# SterownikOswietlenia.net
KiCad netlist of a schematic drawn in EAGLE
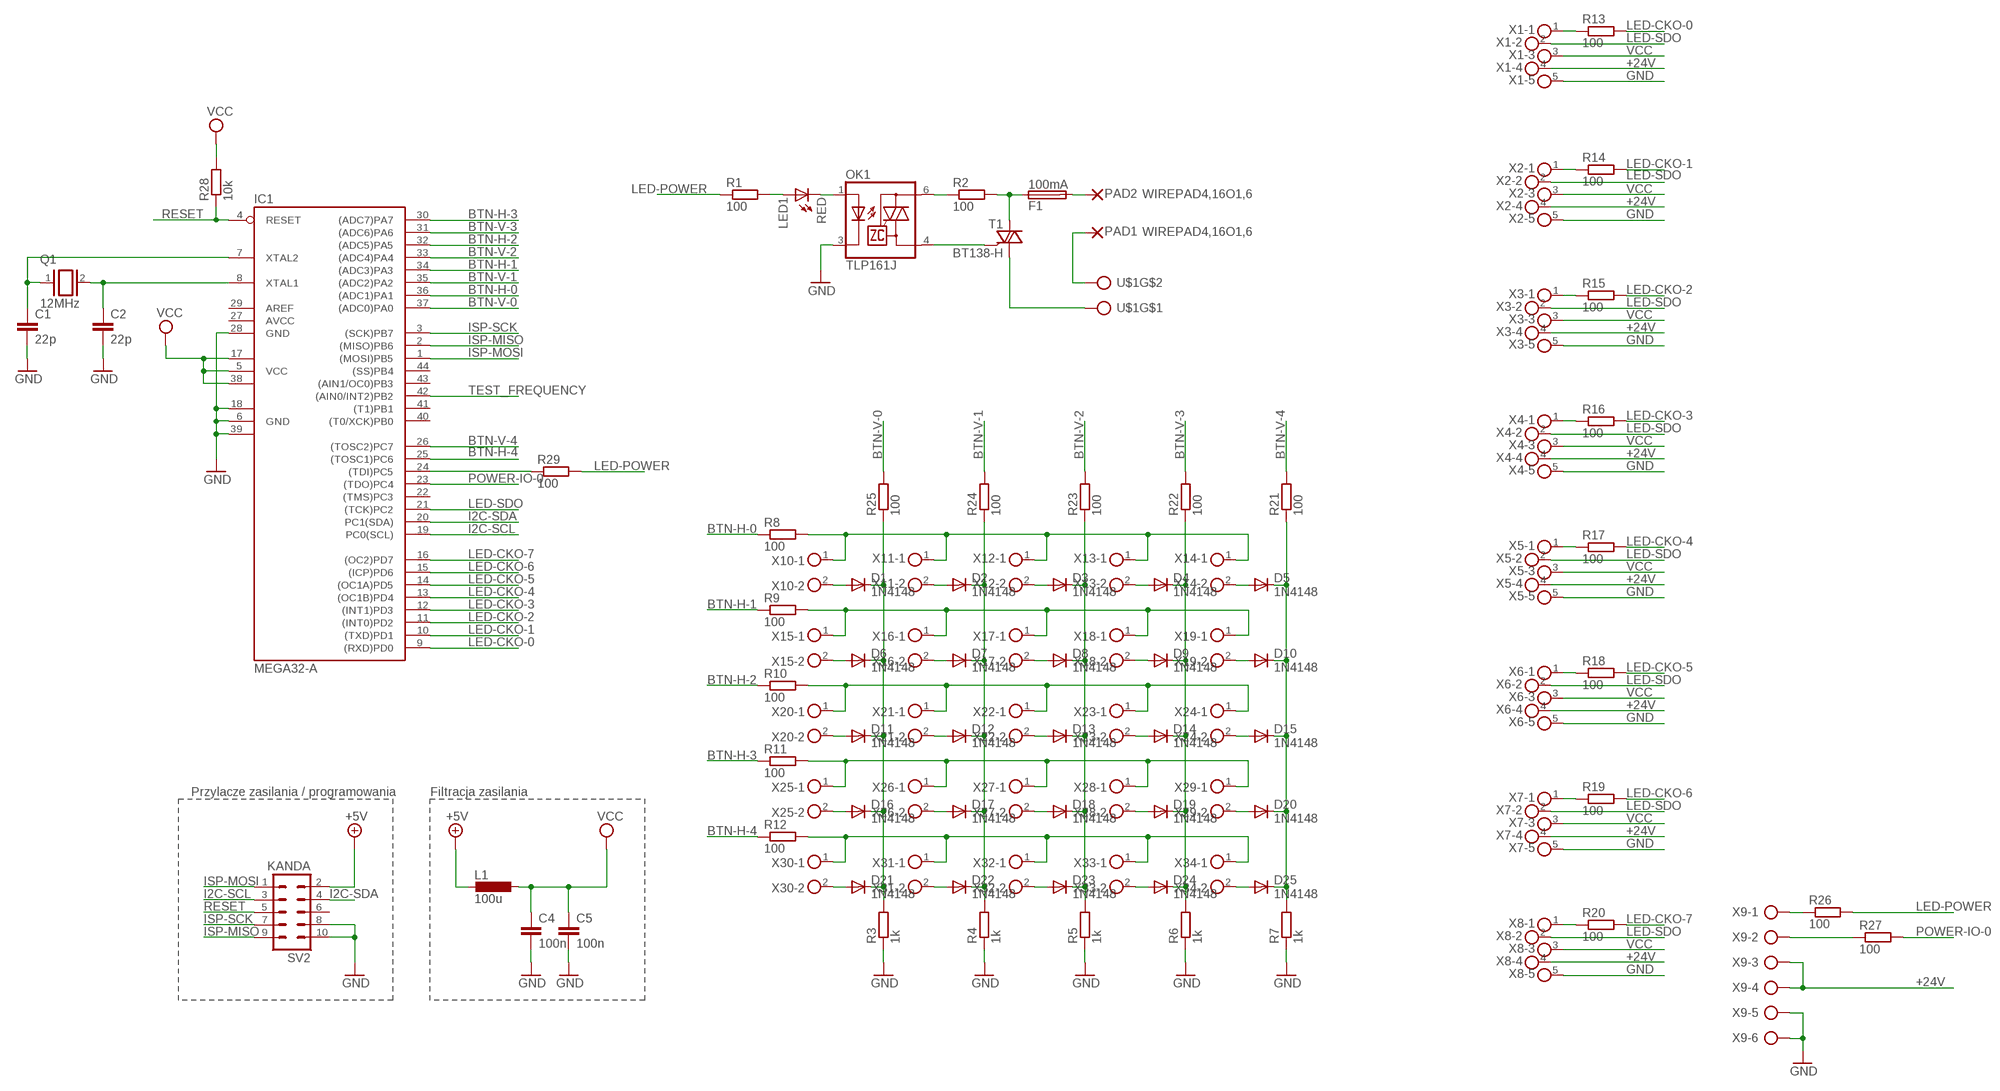
[diagram p0: schematic, sheet 1]

(export (version "E")
  (design (tool "Eeschema 10.0.6"))
  (components
    (comp (ref "C1")
      (value "22p")
      (footprint "eagle-import:C1206")
      (libsource (lib "eagle-import") (part "C-EUC1206"))
    )
    (comp (ref "C2")
      (value "22p")
      (footprint "eagle-import:C1206")
      (libsource (lib "eagle-import") (part "C-EUC1206"))
    )
    (comp (ref "C4")
      (value "100n")
      (footprint "eagle-import:C1206")
      (libsource (lib "eagle-import") (part "C-EUC1206"))
    )
    (comp (ref "C5")
      (value "100n")
      (footprint "eagle-import:C1206")
      (libsource (lib "eagle-import") (part "C-EUC1206"))
    )
    (comp (ref "D1")
      (value "1N4148")
      (footprint "eagle-import:MINIMELF")
      (libsource (lib "eagle-import") (part "DIODE-MINIMELF"))
    )
    (comp (ref "D2")
      (value "1N4148")
      (footprint "eagle-import:MINIMELF")
      (libsource (lib "eagle-import") (part "DIODE-MINIMELF"))
    )
    (comp (ref "D3")
      (value "1N4148")
      (footprint "eagle-import:MINIMELF")
      (libsource (lib "eagle-import") (part "DIODE-MINIMELF"))
    )
    (comp (ref "D4")
      (value "1N4148")
      (footprint "eagle-import:MINIMELF")
      (libsource (lib "eagle-import") (part "DIODE-MINIMELF"))
    )
    (comp (ref "D5")
      (value "1N4148")
      (footprint "eagle-import:MINIMELF")
      (libsource (lib "eagle-import") (part "DIODE-MINIMELF"))
    )
    (comp (ref "D6")
      (value "1N4148")
      (footprint "eagle-import:MINIMELF")
      (libsource (lib "eagle-import") (part "DIODE-MINIMELF"))
    )
    (comp (ref "D7")
      (value "1N4148")
      (footprint "eagle-import:MINIMELF")
      (libsource (lib "eagle-import") (part "DIODE-MINIMELF"))
    )
    (comp (ref "D8")
      (value "1N4148")
      (footprint "eagle-import:MINIMELF")
      (libsource (lib "eagle-import") (part "DIODE-MINIMELF"))
    )
    (comp (ref "D9")
      (value "1N4148")
      (footprint "eagle-import:MINIMELF")
      (libsource (lib "eagle-import") (part "DIODE-MINIMELF"))
    )
    (comp (ref "D10")
      (value "1N4148")
      (footprint "eagle-import:MINIMELF")
      (libsource (lib "eagle-import") (part "DIODE-MINIMELF"))
    )
    (comp (ref "D11")
      (value "1N4148")
      (footprint "eagle-import:MINIMELF")
      (libsource (lib "eagle-import") (part "DIODE-MINIMELF"))
    )
    (comp (ref "D12")
      (value "1N4148")
      (footprint "eagle-import:MINIMELF")
      (libsource (lib "eagle-import") (part "DIODE-MINIMELF"))
    )
    (comp (ref "D13")
      (value "1N4148")
      (footprint "eagle-import:MINIMELF")
      (libsource (lib "eagle-import") (part "DIODE-MINIMELF"))
    )
    (comp (ref "D14")
      (value "1N4148")
      (footprint "eagle-import:MINIMELF")
      (libsource (lib "eagle-import") (part "DIODE-MINIMELF"))
    )
    (comp (ref "D15")
      (value "1N4148")
      (footprint "eagle-import:MINIMELF")
      (libsource (lib "eagle-import") (part "DIODE-MINIMELF"))
    )
    (comp (ref "D16")
      (value "1N4148")
      (footprint "eagle-import:MINIMELF")
      (libsource (lib "eagle-import") (part "DIODE-MINIMELF"))
    )
    (comp (ref "D17")
      (value "1N4148")
      (footprint "eagle-import:MINIMELF")
      (libsource (lib "eagle-import") (part "DIODE-MINIMELF"))
    )
    (comp (ref "D18")
      (value "1N4148")
      (footprint "eagle-import:MINIMELF")
      (libsource (lib "eagle-import") (part "DIODE-MINIMELF"))
    )
    (comp (ref "D19")
      (value "1N4148")
      (footprint "eagle-import:MINIMELF")
      (libsource (lib "eagle-import") (part "DIODE-MINIMELF"))
    )
    (comp (ref "D20")
      (value "1N4148")
      (footprint "eagle-import:MINIMELF")
      (libsource (lib "eagle-import") (part "DIODE-MINIMELF"))
    )
    (comp (ref "D21")
      (value "1N4148")
      (footprint "eagle-import:MINIMELF")
      (libsource (lib "eagle-import") (part "DIODE-MINIMELF"))
    )
    (comp (ref "D22")
      (value "1N4148")
      (footprint "eagle-import:MINIMELF")
      (libsource (lib "eagle-import") (part "DIODE-MINIMELF"))
    )
    (comp (ref "D23")
      (value "1N4148")
      (footprint "eagle-import:MINIMELF")
      (libsource (lib "eagle-import") (part "DIODE-MINIMELF"))
    )
    (comp (ref "D24")
      (value "1N4148")
      (footprint "eagle-import:MINIMELF")
      (libsource (lib "eagle-import") (part "DIODE-MINIMELF"))
    )
    (comp (ref "D25")
      (value "1N4148")
      (footprint "eagle-import:MINIMELF")
      (libsource (lib "eagle-import") (part "DIODE-MINIMELF"))
    )
    (comp (ref "F1")
      (value "100mA")
      (footprint "eagle-import:F457")
      (libsource (lib "eagle-import") (part "F457"))
    )
    (comp (ref "IC1")
      (value "MEGA32-A")
      (footprint "eagle-import:TQFP44")
      (fields (field (name "MPN") "ATMEGA32-16AU"))
      (libsource (lib "eagle-import") (part "MEGA32-A"))
    )
    (comp (ref "L1")
      (value "100u")
      (footprint "eagle-import:R1210")
      (libsource (lib "eagle-import") (part "L-EUL1210"))
    )
    (comp (ref "LED1")
      (value "RED")
      (footprint "eagle-import:LED3MM")
      (libsource (lib "eagle-import") (part "LED3MM"))
    )
    (comp (ref "OK1")
      (value "TLP161J")
      (footprint "eagle-import:MFP4")
      (libsource (lib "eagle-import") (part "TLP161J"))
    )
    (comp (ref "PAD1")
      (value "WIREPAD4,16O1,6")
      (footprint "eagle-import:4,16O1,6")
      (libsource (lib "eagle-import") (part "WIREPAD4,16O1,6"))
    )
    (comp (ref "PAD2")
      (value "WIREPAD4,16O1,6")
      (footprint "eagle-import:4,16O1,6")
      (libsource (lib "eagle-import") (part "WIREPAD4,16O1,6"))
    )
    (comp (ref "Q1")
      (value "12MHz")
      (footprint "eagle-import:QS")
      (libsource (lib "eagle-import") (part "XTAL/S"))
    )
    (comp (ref "R1")
      (value "100")
      (footprint "eagle-import:R1206")
      (libsource (lib "eagle-import") (part "R-EU_R1206"))
    )
    (comp (ref "R2")
      (value "100")
      (footprint "eagle-import:R1206")
      (libsource (lib "eagle-import") (part "R-EU_R1206"))
    )
    (comp (ref "R3")
      (value "1k")
      (footprint "eagle-import:R1206")
      (libsource (lib "eagle-import") (part "R-EU_R1206"))
    )
    (comp (ref "R4")
      (value "1k")
      (footprint "eagle-import:R1206")
      (libsource (lib "eagle-import") (part "R-EU_R1206"))
    )
    (comp (ref "R5")
      (value "1k")
      (footprint "eagle-import:R1206")
      (libsource (lib "eagle-import") (part "R-EU_R1206"))
    )
    (comp (ref "R6")
      (value "1k")
      (footprint "eagle-import:R1206")
      (libsource (lib "eagle-import") (part "R-EU_R1206"))
    )
    (comp (ref "R7")
      (value "1k")
      (footprint "eagle-import:R1206")
      (libsource (lib "eagle-import") (part "R-EU_R1206"))
    )
    (comp (ref "R8")
      (value "100")
      (footprint "eagle-import:R1206")
      (libsource (lib "eagle-import") (part "R-EU_R1206"))
    )
    (comp (ref "R9")
      (value "100")
      (footprint "eagle-import:R1206")
      (libsource (lib "eagle-import") (part "R-EU_R1206"))
    )
    (comp (ref "R10")
      (value "100")
      (footprint "eagle-import:R1206")
      (libsource (lib "eagle-import") (part "R-EU_R1206"))
    )
    (comp (ref "R11")
      (value "100")
      (footprint "eagle-import:R1206")
      (libsource (lib "eagle-import") (part "R-EU_R1206"))
    )
    (comp (ref "R12")
      (value "100")
      (footprint "eagle-import:R1206")
      (libsource (lib "eagle-import") (part "R-EU_R1206"))
    )
    (comp (ref "R13")
      (value "100")
      (footprint "eagle-import:R1206")
      (libsource (lib "eagle-import") (part "R-EU_R1206"))
    )
    (comp (ref "R14")
      (value "100")
      (footprint "eagle-import:R1206")
      (libsource (lib "eagle-import") (part "R-EU_R1206"))
    )
    (comp (ref "R15")
      (value "100")
      (footprint "eagle-import:R1206")
      (libsource (lib "eagle-import") (part "R-EU_R1206"))
    )
    (comp (ref "R16")
      (value "100")
      (footprint "eagle-import:R1206")
      (libsource (lib "eagle-import") (part "R-EU_R1206"))
    )
    (comp (ref "R17")
      (value "100")
      (footprint "eagle-import:R1206")
      (libsource (lib "eagle-import") (part "R-EU_R1206"))
    )
    (comp (ref "R18")
      (value "100")
      (footprint "eagle-import:R1206")
      (libsource (lib "eagle-import") (part "R-EU_R1206"))
    )
    (comp (ref "R19")
      (value "100")
      (footprint "eagle-import:R1206")
      (libsource (lib "eagle-import") (part "R-EU_R1206"))
    )
    (comp (ref "R20")
      (value "100")
      (footprint "eagle-import:R1206")
      (libsource (lib "eagle-import") (part "R-EU_R1206"))
    )
    (comp (ref "R21")
      (value "100")
      (footprint "eagle-import:R1206")
      (libsource (lib "eagle-import") (part "R-EU_R1206"))
    )
    (comp (ref "R22")
      (value "100")
      (footprint "eagle-import:R1206")
      (libsource (lib "eagle-import") (part "R-EU_R1206"))
    )
    (comp (ref "R23")
      (value "100")
      (footprint "eagle-import:R1206")
      (libsource (lib "eagle-import") (part "R-EU_R1206"))
    )
    (comp (ref "R24")
      (value "100")
      (footprint "eagle-import:R1206")
      (libsource (lib "eagle-import") (part "R-EU_R1206"))
    )
    (comp (ref "R25")
      (value "100")
      (footprint "eagle-import:R1206")
      (libsource (lib "eagle-import") (part "R-EU_R1206"))
    )
    (comp (ref "R26")
      (value "100")
      (footprint "eagle-import:R1206")
      (libsource (lib "eagle-import") (part "R-EU_R1206"))
    )
    (comp (ref "R27")
      (value "100")
      (footprint "eagle-import:R1206")
      (libsource (lib "eagle-import") (part "R-EU_R1206"))
    )
    (comp (ref "R28")
      (value "10k")
      (footprint "eagle-import:R1206")
      (libsource (lib "eagle-import") (part "R-EU_R1206"))
    )
    (comp (ref "R29")
      (value "100")
      (footprint "eagle-import:R1206")
      (libsource (lib "eagle-import") (part "R-EU_R1206"))
    )
    (comp (ref "SV2")
      (value "KANDA")
      (footprint "eagle-import:ML10L")
      (libsource (lib "eagle-import") (part "ML10L"))
    )
    (comp (ref "T1")
      (value "BT138-H")
      (footprint "eagle-import:TO220BH")
      (libsource (lib "eagle-import") (part "BT138-H"))
    )
    (comp (ref "U$1")
      (value "AK3001-2")
      (footprint "eagle-import:AK3001-2")
      (libsource (lib "eagle-import") (part "AK3001-2"))
    )
    (comp (ref "X1")
      (value "AKL59-05")
      (footprint "eagle-import:5POL35")
      (libsource (lib "eagle-import") (part "AKL59-05"))
    )
    (comp (ref "X2")
      (value "AKL59-05")
      (footprint "eagle-import:5POL35")
      (libsource (lib "eagle-import") (part "AKL59-05"))
    )
    (comp (ref "X3")
      (value "AKL59-05")
      (footprint "eagle-import:5POL35")
      (libsource (lib "eagle-import") (part "AKL59-05"))
    )
    (comp (ref "X4")
      (value "AKL59-05")
      (footprint "eagle-import:5POL35")
      (libsource (lib "eagle-import") (part "AKL59-05"))
    )
    (comp (ref "X5")
      (value "AKL59-05")
      (footprint "eagle-import:5POL35")
      (libsource (lib "eagle-import") (part "AKL59-05"))
    )
    (comp (ref "X6")
      (value "AKL59-05")
      (footprint "eagle-import:5POL35")
      (libsource (lib "eagle-import") (part "AKL59-05"))
    )
    (comp (ref "X7")
      (value "AKL59-05")
      (footprint "eagle-import:5POL35")
      (libsource (lib "eagle-import") (part "AKL59-05"))
    )
    (comp (ref "X8")
      (value "AKL59-05")
      (footprint "eagle-import:5POL35")
      (libsource (lib "eagle-import") (part "AKL59-05"))
    )
    (comp (ref "X9")
      (value "AK500/6")
      (footprint "eagle-import:AK500_6")
      (libsource (lib "eagle-import") (part "AK500/6"))
    )
    (comp (ref "X10")
      (value "AKL59-02")
      (footprint "eagle-import:2POL35")
      (libsource (lib "eagle-import") (part "AKL59-02"))
    )
    (comp (ref "X11")
      (value "AKL59-02")
      (footprint "eagle-import:2POL35")
      (libsource (lib "eagle-import") (part "AKL59-02"))
    )
    (comp (ref "X12")
      (value "AKL59-02")
      (footprint "eagle-import:2POL35")
      (libsource (lib "eagle-import") (part "AKL59-02"))
    )
    (comp (ref "X13")
      (value "AKL59-02")
      (footprint "eagle-import:2POL35")
      (libsource (lib "eagle-import") (part "AKL59-02"))
    )
    (comp (ref "X14")
      (value "AKL59-02")
      (footprint "eagle-import:2POL35")
      (libsource (lib "eagle-import") (part "AKL59-02"))
    )
    (comp (ref "X15")
      (value "AKL59-02")
      (footprint "eagle-import:2POL35")
      (libsource (lib "eagle-import") (part "AKL59-02"))
    )
    (comp (ref "X16")
      (value "AKL59-02")
      (footprint "eagle-import:2POL35")
      (libsource (lib "eagle-import") (part "AKL59-02"))
    )
    (comp (ref "X17")
      (value "AKL59-02")
      (footprint "eagle-import:2POL35")
      (libsource (lib "eagle-import") (part "AKL59-02"))
    )
    (comp (ref "X18")
      (value "AKL59-02")
      (footprint "eagle-import:2POL35")
      (libsource (lib "eagle-import") (part "AKL59-02"))
    )
    (comp (ref "X19")
      (value "AKL59-02")
      (footprint "eagle-import:2POL35")
      (libsource (lib "eagle-import") (part "AKL59-02"))
    )
    (comp (ref "X20")
      (value "AKL59-02")
      (footprint "eagle-import:2POL35")
      (libsource (lib "eagle-import") (part "AKL59-02"))
    )
    (comp (ref "X21")
      (value "AKL59-02")
      (footprint "eagle-import:2POL35")
      (libsource (lib "eagle-import") (part "AKL59-02"))
    )
    (comp (ref "X22")
      (value "AKL59-02")
      (footprint "eagle-import:2POL35")
      (libsource (lib "eagle-import") (part "AKL59-02"))
    )
    (comp (ref "X23")
      (value "AKL59-02")
      (footprint "eagle-import:2POL35")
      (libsource (lib "eagle-import") (part "AKL59-02"))
    )
    (comp (ref "X24")
      (value "AKL59-02")
      (footprint "eagle-import:2POL35")
      (libsource (lib "eagle-import") (part "AKL59-02"))
    )
    (comp (ref "X25")
      (value "AKL59-02")
      (footprint "eagle-import:2POL35")
      (libsource (lib "eagle-import") (part "AKL59-02"))
    )
    (comp (ref "X26")
      (value "AKL59-02")
      (footprint "eagle-import:2POL35")
      (libsource (lib "eagle-import") (part "AKL59-02"))
    )
    (comp (ref "X27")
      (value "AKL59-02")
      (footprint "eagle-import:2POL35")
      (libsource (lib "eagle-import") (part "AKL59-02"))
    )
    (comp (ref "X28")
      (value "AKL59-02")
      (footprint "eagle-import:2POL35")
      (libsource (lib "eagle-import") (part "AKL59-02"))
    )
    (comp (ref "X29")
      (value "AKL59-02")
      (footprint "eagle-import:2POL35")
      (libsource (lib "eagle-import") (part "AKL59-02"))
    )
    (comp (ref "X30")
      (value "AKL59-02")
      (footprint "eagle-import:2POL35")
      (libsource (lib "eagle-import") (part "AKL59-02"))
    )
    (comp (ref "X31")
      (value "AKL59-02")
      (footprint "eagle-import:2POL35")
      (libsource (lib "eagle-import") (part "AKL59-02"))
    )
    (comp (ref "X32")
      (value "AKL59-02")
      (footprint "eagle-import:2POL35")
      (libsource (lib "eagle-import") (part "AKL59-02"))
    )
    (comp (ref "X33")
      (value "AKL59-02")
      (footprint "eagle-import:2POL35")
      (libsource (lib "eagle-import") (part "AKL59-02"))
    )
    (comp (ref "X34")
      (value "AKL59-02")
      (footprint "eagle-import:2POL35")
      (libsource (lib "eagle-import") (part "AKL59-02"))
    )
  )
  (nets
    (net (code "1") (name "+5V") (class "Default")
      (node (ref "L1") (pin "2") (pinfunction "2_2") (pintype "passive"))
      (node (ref "SV2") (pin "2") (pinfunction "2_2") (pintype "passive"))
    )
    (net (code "2") (name "/+24V") (class "Default")
      (node (ref "X1") (pin "4") (pinfunction "1_4") (pintype "passive"))
      (node (ref "X2") (pin "4") (pinfunction "1_4") (pintype "passive"))
      (node (ref "X3") (pin "4") (pinfunction "1_4") (pintype "passive"))
      (node (ref "X4") (pin "4") (pinfunction "1_4") (pintype "passive"))
      (node (ref "X5") (pin "4") (pinfunction "1_4") (pintype "passive"))
      (node (ref "X6") (pin "4") (pinfunction "1_4") (pintype "passive"))
      (node (ref "X7") (pin "4") (pinfunction "1_4") (pintype "passive"))
      (node (ref "X8") (pin "4") (pinfunction "1_4") (pintype "passive"))
      (node (ref "X9") (pin "3") (pinfunction "KL_3") (pintype "passive"))
      (node (ref "X9") (pin "4") (pinfunction "KL_4") (pintype "passive"))
    )
    (net (code "3") (name "/AVCC") (class "Default")
      (node (ref "IC1") (pin "27") (pinfunction "AVCC_27") (pintype "power_in"))
    )
    (net (code "4") (name "/BTN-H-0") (class "Default")
      (node (ref "IC1") (pin "36") (pinfunction "(ADC1)PA1_36") (pintype "bidirectional"))
      (node (ref "R8") (pin "1") (pinfunction "1_1") (pintype "passive"))
    )
    (net (code "5") (name "/BTN-H-1") (class "Default")
      (node (ref "IC1") (pin "34") (pinfunction "(ADC3)PA3_34") (pintype "bidirectional"))
      (node (ref "R9") (pin "1") (pinfunction "1_1") (pintype "passive"))
    )
    (net (code "6") (name "/BTN-H-2") (class "Default")
      (node (ref "IC1") (pin "32") (pinfunction "(ADC5)PA5_32") (pintype "bidirectional"))
      (node (ref "R10") (pin "1") (pinfunction "1_1") (pintype "passive"))
    )
    (net (code "7") (name "/BTN-H-3") (class "Default")
      (node (ref "IC1") (pin "30") (pinfunction "(ADC7)PA7_30") (pintype "bidirectional"))
      (node (ref "R11") (pin "1") (pinfunction "1_1") (pintype "passive"))
    )
    (net (code "8") (name "/BTN-H-4") (class "Default")
      (node (ref "IC1") (pin "25") (pinfunction "(TOSC1)PC6_25") (pintype "bidirectional"))
      (node (ref "R12") (pin "1") (pinfunction "1_1") (pintype "passive"))
    )
    (net (code "9") (name "/BTN-V-0") (class "Default")
      (node (ref "IC1") (pin "37") (pinfunction "(ADC0)PA0_37") (pintype "bidirectional"))
      (node (ref "R25") (pin "2") (pinfunction "2_2") (pintype "passive"))
    )
    (net (code "10") (name "/BTN-V-1") (class "Default")
      (node (ref "IC1") (pin "35") (pinfunction "(ADC2)PA2_35") (pintype "bidirectional"))
      (node (ref "R24") (pin "2") (pinfunction "2_2") (pintype "passive"))
    )
    (net (code "11") (name "/BTN-V-2") (class "Default")
      (node (ref "IC1") (pin "33") (pinfunction "(ADC4)PA4_33") (pintype "bidirectional"))
      (node (ref "R23") (pin "2") (pinfunction "2_2") (pintype "passive"))
    )
    (net (code "12") (name "/BTN-V-3") (class "Default")
      (node (ref "IC1") (pin "31") (pinfunction "(ADC6)PA6_31") (pintype "bidirectional"))
      (node (ref "R22") (pin "2") (pinfunction "2_2") (pintype "passive"))
    )
    (net (code "13") (name "/BTN-V-4") (class "Default")
      (node (ref "IC1") (pin "26") (pinfunction "(TOSC2)PC7_26") (pintype "bidirectional"))
      (node (ref "R21") (pin "2") (pinfunction "2_2") (pintype "passive"))
    )
    (net (code "14") (name "/I2C-SCL") (class "Default")
      (node (ref "IC1") (pin "19") (pinfunction "PC0(SCL)_19") (pintype "bidirectional"))
      (node (ref "SV2") (pin "3") (pinfunction "3_3") (pintype "passive"))
    )
    (net (code "15") (name "/I2C-SDA") (class "Default")
      (node (ref "IC1") (pin "20") (pinfunction "PC1(SDA)_20") (pintype "bidirectional"))
      (node (ref "SV2") (pin "4") (pinfunction "4_4") (pintype "passive"))
    )
    (net (code "16") (name "/ISP-MISO") (class "Default")
      (node (ref "IC1") (pin "2") (pinfunction "(MISO)PB6_2") (pintype "bidirectional"))
      (node (ref "SV2") (pin "9") (pinfunction "9_9") (pintype "passive"))
    )
    (net (code "17") (name "/ISP-MOSI") (class "Default")
      (node (ref "IC1") (pin "1") (pinfunction "(MOSI)PB5_1") (pintype "bidirectional"))
      (node (ref "SV2") (pin "1") (pinfunction "1_1") (pintype "passive"))
    )
    (net (code "18") (name "/ISP-SCK") (class "Default")
      (node (ref "IC1") (pin "3") (pinfunction "(SCK)PB7_3") (pintype "bidirectional"))
      (node (ref "SV2") (pin "7") (pinfunction "7_7") (pintype "passive"))
    )
    (net (code "19") (name "/LED-CKO-0") (class "Default")
      (node (ref "IC1") (pin "9") (pinfunction "(RXD)PD0_9") (pintype "bidirectional"))
      (node (ref "R13") (pin "2") (pinfunction "2_2") (pintype "passive"))
    )
    (net (code "20") (name "/LED-CKO-1") (class "Default")
      (node (ref "IC1") (pin "10") (pinfunction "(TXD)PD1_10") (pintype "bidirectional"))
      (node (ref "R14") (pin "2") (pinfunction "2_2") (pintype "passive"))
    )
    (net (code "21") (name "/LED-CKO-2") (class "Default")
      (node (ref "IC1") (pin "11") (pinfunction "(INT0)PD2_11") (pintype "bidirectional"))
      (node (ref "R15") (pin "2") (pinfunction "2_2") (pintype "passive"))
    )
    (net (code "22") (name "/LED-CKO-3") (class "Default")
      (node (ref "IC1") (pin "12") (pinfunction "(INT1)PD3_12") (pintype "bidirectional"))
      (node (ref "R16") (pin "2") (pinfunction "2_2") (pintype "passive"))
    )
    (net (code "23") (name "/LED-CKO-4") (class "Default")
      (node (ref "IC1") (pin "13") (pinfunction "(OC1B)PD4_13") (pintype "bidirectional"))
      (node (ref "R17") (pin "2") (pinfunction "2_2") (pintype "passive"))
    )
    (net (code "24") (name "/LED-CKO-5") (class "Default")
      (node (ref "IC1") (pin "14") (pinfunction "(OC1A)PD5_14") (pintype "bidirectional"))
      (node (ref "R18") (pin "2") (pinfunction "2_2") (pintype "passive"))
    )
    (net (code "25") (name "/LED-CKO-6") (class "Default")
      (node (ref "IC1") (pin "15") (pinfunction "(ICP)PD6_15") (pintype "bidirectional"))
      (node (ref "R19") (pin "2") (pinfunction "2_2") (pintype "passive"))
    )
    (net (code "26") (name "/LED-CKO-7") (class "Default")
      (node (ref "IC1") (pin "16") (pinfunction "(OC2)PD7_16") (pintype "bidirectional"))
      (node (ref "R20") (pin "2") (pinfunction "2_2") (pintype "passive"))
    )
    (net (code "27") (name "/LED-POWER") (class "Default")
      (node (ref "R1") (pin "1") (pinfunction "1_1") (pintype "passive"))
      (node (ref "R26") (pin "2") (pinfunction "2_2") (pintype "passive"))
      (node (ref "R29") (pin "2") (pinfunction "2_2") (pintype "passive"))
    )
    (net (code "28") (name "/LED-SDO") (class "Default")
      (node (ref "IC1") (pin "21") (pinfunction "(TCK)PC2_21") (pintype "bidirectional"))
      (node (ref "X1") (pin "2") (pinfunction "1_2") (pintype "passive"))
      (node (ref "X2") (pin "2") (pinfunction "1_2") (pintype "passive"))
      (node (ref "X3") (pin "2") (pinfunction "1_2") (pintype "passive"))
      (node (ref "X4") (pin "2") (pinfunction "1_2") (pintype "passive"))
      (node (ref "X5") (pin "2") (pinfunction "1_2") (pintype "passive"))
      (node (ref "X6") (pin "2") (pinfunction "1_2") (pintype "passive"))
      (node (ref "X7") (pin "2") (pinfunction "1_2") (pintype "passive"))
      (node (ref "X8") (pin "2") (pinfunction "1_2") (pintype "passive"))
    )
    (net (code "29") (name "/POWER-IO-0") (class "Default")
      (node (ref "IC1") (pin "23") (pinfunction "(TDO)PC4_23") (pintype "bidirectional"))
      (node (ref "R27") (pin "2") (pinfunction "2_2") (pintype "passive"))
    )
    (net (code "30") (name "/RESET") (class "Default")
      (node (ref "IC1") (pin "4") (pinfunction "RESET_4") (pintype "input"))
      (node (ref "R28") (pin "1") (pinfunction "1_1") (pintype "passive"))
      (node (ref "SV2") (pin "5") (pinfunction "5_5") (pintype "passive"))
    )
    (net (code "31") (name "/TEST_FREQUENCY") (class "Default")
      (node (ref "IC1") (pin "42") (pinfunction "(AIN0/INT2)PB2_42") (pintype "bidirectional"))
    )
    (net (code "32") (name "GND") (class "Default")
      (node (ref "C1") (pin "2") (pinfunction "2_2") (pintype "passive"))
      (node (ref "C2") (pin "2") (pinfunction "2_2") (pintype "passive"))
      (node (ref "C4") (pin "2") (pinfunction "2_2") (pintype "passive"))
      (node (ref "C5") (pin "2") (pinfunction "2_2") (pintype "passive"))
      (node (ref "IC1") (pin "18") (pinfunction "GND1_18") (pintype "power_in"))
      (node (ref "IC1") (pin "28") (pinfunction "GND_28") (pintype "power_in"))
      (node (ref "IC1") (pin "39") (pinfunction "GND2_39") (pintype "power_in"))
      (node (ref "IC1") (pin "6") (pinfunction "GND_6") (pintype "power_in"))
      (node (ref "OK1") (pin "3") (pinfunction "C_3") (pintype "passive"))
      (node (ref "R3") (pin "1") (pinfunction "1_1") (pintype "passive"))
      (node (ref "R4") (pin "1") (pinfunction "1_1") (pintype "passive"))
      (node (ref "R5") (pin "1") (pinfunction "1_1") (pintype "passive"))
      (node (ref "R6") (pin "1") (pinfunction "1_1") (pintype "passive"))
      (node (ref "R7") (pin "1") (pinfunction "1_1") (pintype "passive"))
      (node (ref "SV2") (pin "10") (pinfunction "10_10") (pintype "passive"))
      (node (ref "SV2") (pin "8") (pinfunction "8_8") (pintype "passive"))
      (node (ref "X1") (pin "5") (pinfunction "1_5") (pintype "passive"))
      (node (ref "X2") (pin "5") (pinfunction "1_5") (pintype "passive"))
      (node (ref "X3") (pin "5") (pinfunction "1_5") (pintype "passive"))
      (node (ref "X4") (pin "5") (pinfunction "1_5") (pintype "passive"))
      (node (ref "X5") (pin "5") (pinfunction "1_5") (pintype "passive"))
      (node (ref "X6") (pin "5") (pinfunction "1_5") (pintype "passive"))
      (node (ref "X7") (pin "5") (pinfunction "1_5") (pintype "passive"))
      (node (ref "X8") (pin "5") (pinfunction "1_5") (pintype "passive"))
      (node (ref "X9") (pin "5") (pinfunction "KL_5") (pintype "passive"))
      (node (ref "X9") (pin "6") (pinfunction "KL_6") (pintype "passive"))
    )
    (net (code "33") (name "Net-(D1-PadC)") (class "Default")
      (node (ref "D1") (pin "C") (pinfunction "C_C") (pintype "passive"))
      (node (ref "D11") (pin "C") (pinfunction "C_C") (pintype "passive"))
      (node (ref "D16") (pin "C") (pinfunction "C_C") (pintype "passive"))
      (node (ref "D21") (pin "C") (pinfunction "C_C") (pintype "passive"))
      (node (ref "D6") (pin "C") (pinfunction "C_C") (pintype "passive"))
      (node (ref "R25") (pin "1") (pinfunction "1_1") (pintype "passive"))
      (node (ref "R3") (pin "2") (pinfunction "2_2") (pintype "passive"))
    )
    (net (code "34") (name "Net-(D10-PadC)") (class "Default")
      (node (ref "D10") (pin "C") (pinfunction "C_C") (pintype "passive"))
      (node (ref "D15") (pin "C") (pinfunction "C_C") (pintype "passive"))
      (node (ref "D20") (pin "C") (pinfunction "C_C") (pintype "passive"))
      (node (ref "D25") (pin "C") (pinfunction "C_C") (pintype "passive"))
      (node (ref "D5") (pin "C") (pinfunction "C_C") (pintype "passive"))
      (node (ref "R21") (pin "1") (pinfunction "1_1") (pintype "passive"))
      (node (ref "R7") (pin "2") (pinfunction "2_2") (pintype "passive"))
    )
    (net (code "35") (name "Net-(D12-PadC)") (class "Default")
      (node (ref "D12") (pin "C") (pinfunction "C_C") (pintype "passive"))
      (node (ref "D17") (pin "C") (pinfunction "C_C") (pintype "passive"))
      (node (ref "D2") (pin "C") (pinfunction "C_C") (pintype "passive"))
      (node (ref "D22") (pin "C") (pinfunction "C_C") (pintype "passive"))
      (node (ref "D7") (pin "C") (pinfunction "C_C") (pintype "passive"))
      (node (ref "R24") (pin "1") (pinfunction "1_1") (pintype "passive"))
      (node (ref "R4") (pin "2") (pinfunction "2_2") (pintype "passive"))
    )
    (net (code "36") (name "Net-(D13-PadC)") (class "Default")
      (node (ref "D13") (pin "C") (pinfunction "C_C") (pintype "passive"))
      (node (ref "D18") (pin "C") (pinfunction "C_C") (pintype "passive"))
      (node (ref "D23") (pin "C") (pinfunction "C_C") (pintype "passive"))
      (node (ref "D3") (pin "C") (pinfunction "C_C") (pintype "passive"))
      (node (ref "D8") (pin "C") (pinfunction "C_C") (pintype "passive"))
      (node (ref "R23") (pin "1") (pinfunction "1_1") (pintype "passive"))
      (node (ref "R5") (pin "2") (pinfunction "2_2") (pintype "passive"))
    )
    (net (code "37") (name "Net-(D14-PadC)") (class "Default")
      (node (ref "D14") (pin "C") (pinfunction "C_C") (pintype "passive"))
      (node (ref "D19") (pin "C") (pinfunction "C_C") (pintype "passive"))
      (node (ref "D24") (pin "C") (pinfunction "C_C") (pintype "passive"))
      (node (ref "D4") (pin "C") (pinfunction "C_C") (pintype "passive"))
      (node (ref "D9") (pin "C") (pinfunction "C_C") (pintype "passive"))
      (node (ref "R22") (pin "1") (pinfunction "1_1") (pintype "passive"))
      (node (ref "R6") (pin "2") (pinfunction "2_2") (pintype "passive"))
    )
    (net (code "38") (name "Net-(IC1-(TDI)PC5)") (class "Default")
      (node (ref "IC1") (pin "24") (pinfunction "(TDI)PC5_24") (pintype "bidirectional"))
      (node (ref "R29") (pin "1") (pinfunction "1_1") (pintype "passive"))
    )
    (net (code "39") (name "Net-(IC1-XTAL1)") (class "Default")
      (node (ref "C2") (pin "1") (pinfunction "1_1") (pintype "passive"))
      (node (ref "IC1") (pin "8") (pinfunction "XTAL1_8") (pintype "bidirectional"))
      (node (ref "Q1") (pin "2") (pinfunction "2_2") (pintype "passive"))
    )
    (net (code "40") (name "Net-(IC1-XTAL2)") (class "Default")
      (node (ref "C1") (pin "1") (pinfunction "1_1") (pintype "passive"))
      (node (ref "IC1") (pin "7") (pinfunction "XTAL2_7") (pintype "bidirectional"))
      (node (ref "Q1") (pin "1") (pinfunction "1_1") (pintype "passive"))
    )
    (net (code "41") (name "Net-(LED1-C)") (class "Default")
      (node (ref "LED1") (pin "K") (pinfunction "C_K") (pintype "passive"))
      (node (ref "OK1") (pin "1") (pinfunction "A_1") (pintype "passive"))
    )
    (net (code "42") (name "Net-(LED1-PadA)") (class "Default")
      (node (ref "LED1") (pin "A") (pinfunction "A_A") (pintype "passive"))
      (node (ref "R1") (pin "2") (pinfunction "2_2") (pintype "passive"))
    )
    (net (code "43") (name "Net-(OK1-A1)") (class "Default")
      (node (ref "OK1") (pin "4") (pinfunction "A1_4") (pintype "passive"))
      (node (ref "T1") (pin "G") (pinfunction "G_G") (pintype "passive"))
    )
    (net (code "44") (name "Net-(OK1-A2)") (class "Default")
      (node (ref "OK1") (pin "6") (pinfunction "A2_6") (pintype "passive"))
      (node (ref "R2") (pin "1") (pinfunction "1_1") (pintype "passive"))
    )
    (net (code "45") (name "Net-(PAD1-P)") (class "Default")
      (node (ref "PAD1") (pin "1") (pinfunction "P_1") (pintype "passive"))
      (node (ref "U$1") (pin "P$3") (pinfunction "KL_P$3") (pintype "passive"))
      (node (ref "U$1") (pin "P$4") (pinfunction "KL_P$4") (pintype "passive"))
    )
    (net (code "46") (name "Net-(PAD2-P)") (class "Default")
      (node (ref "F1") (pin "2") (pinfunction "2_2") (pintype "passive"))
      (node (ref "PAD2") (pin "1") (pinfunction "P_1") (pintype "passive"))
    )
    (net (code "47") (name "Net-(R8-Pad2)") (class "Default")
      (node (ref "R8") (pin "2") (pinfunction "2_2") (pintype "passive"))
      (node (ref "X10") (pin "1") (pinfunction "1_1") (pintype "passive"))
      (node (ref "X11") (pin "1") (pinfunction "1_1") (pintype "passive"))
      (node (ref "X12") (pin "1") (pinfunction "1_1") (pintype "passive"))
      (node (ref "X13") (pin "1") (pinfunction "1_1") (pintype "passive"))
      (node (ref "X14") (pin "1") (pinfunction "1_1") (pintype "passive"))
    )
    (net (code "48") (name "Net-(R9-Pad2)") (class "Default")
      (node (ref "R9") (pin "2") (pinfunction "2_2") (pintype "passive"))
      (node (ref "X15") (pin "1") (pinfunction "1_1") (pintype "passive"))
      (node (ref "X16") (pin "1") (pinfunction "1_1") (pintype "passive"))
      (node (ref "X17") (pin "1") (pinfunction "1_1") (pintype "passive"))
      (node (ref "X18") (pin "1") (pinfunction "1_1") (pintype "passive"))
      (node (ref "X19") (pin "1") (pinfunction "1_1") (pintype "passive"))
    )
    (net (code "49") (name "Net-(R10-Pad2)") (class "Default")
      (node (ref "R10") (pin "2") (pinfunction "2_2") (pintype "passive"))
      (node (ref "X20") (pin "1") (pinfunction "1_1") (pintype "passive"))
      (node (ref "X21") (pin "1") (pinfunction "1_1") (pintype "passive"))
      (node (ref "X22") (pin "1") (pinfunction "1_1") (pintype "passive"))
      (node (ref "X23") (pin "1") (pinfunction "1_1") (pintype "passive"))
      (node (ref "X24") (pin "1") (pinfunction "1_1") (pintype "passive"))
    )
    (net (code "50") (name "Net-(R11-Pad2)") (class "Default")
      (node (ref "R11") (pin "2") (pinfunction "2_2") (pintype "passive"))
      (node (ref "X25") (pin "1") (pinfunction "1_1") (pintype "passive"))
      (node (ref "X26") (pin "1") (pinfunction "1_1") (pintype "passive"))
      (node (ref "X27") (pin "1") (pinfunction "1_1") (pintype "passive"))
      (node (ref "X28") (pin "1") (pinfunction "1_1") (pintype "passive"))
      (node (ref "X29") (pin "1") (pinfunction "1_1") (pintype "passive"))
    )
    (net (code "51") (name "Net-(R12-Pad2)") (class "Default")
      (node (ref "R12") (pin "2") (pinfunction "2_2") (pintype "passive"))
      (node (ref "X30") (pin "1") (pinfunction "1_1") (pintype "passive"))
      (node (ref "X31") (pin "1") (pinfunction "1_1") (pintype "passive"))
      (node (ref "X32") (pin "1") (pinfunction "1_1") (pintype "passive"))
      (node (ref "X33") (pin "1") (pinfunction "1_1") (pintype "passive"))
      (node (ref "X34") (pin "1") (pinfunction "1_1") (pintype "passive"))
    )
    (net (code "52") (name "Net-(R13-Pad1)") (class "Default")
      (node (ref "R13") (pin "1") (pinfunction "1_1") (pintype "passive"))
      (node (ref "X1") (pin "1") (pinfunction "1_1") (pintype "passive"))
    )
    (net (code "53") (name "Net-(R14-Pad1)") (class "Default")
      (node (ref "R14") (pin "1") (pinfunction "1_1") (pintype "passive"))
      (node (ref "X2") (pin "1") (pinfunction "1_1") (pintype "passive"))
    )
    (net (code "54") (name "Net-(R15-Pad1)") (class "Default")
      (node (ref "R15") (pin "1") (pinfunction "1_1") (pintype "passive"))
      (node (ref "X3") (pin "1") (pinfunction "1_1") (pintype "passive"))
    )
    (net (code "55") (name "Net-(R16-Pad1)") (class "Default")
      (node (ref "R16") (pin "1") (pinfunction "1_1") (pintype "passive"))
      (node (ref "X4") (pin "1") (pinfunction "1_1") (pintype "passive"))
    )
    (net (code "56") (name "Net-(R17-Pad1)") (class "Default")
      (node (ref "R17") (pin "1") (pinfunction "1_1") (pintype "passive"))
      (node (ref "X5") (pin "1") (pinfunction "1_1") (pintype "passive"))
    )
    (net (code "57") (name "Net-(R18-Pad1)") (class "Default")
      (node (ref "R18") (pin "1") (pinfunction "1_1") (pintype "passive"))
      (node (ref "X6") (pin "1") (pinfunction "1_1") (pintype "passive"))
    )
    (net (code "58") (name "Net-(R19-Pad1)") (class "Default")
      (node (ref "R19") (pin "1") (pinfunction "1_1") (pintype "passive"))
      (node (ref "X7") (pin "1") (pinfunction "1_1") (pintype "passive"))
    )
    (net (code "59") (name "Net-(R20-Pad1)") (class "Default")
      (node (ref "R20") (pin "1") (pinfunction "1_1") (pintype "passive"))
      (node (ref "X8") (pin "1") (pinfunction "1_1") (pintype "passive"))
    )
    (net (code "60") (name "Net-(T1-A1)") (class "Default")
      (node (ref "T1") (pin "T1") (pinfunction "A1_T1") (pintype "passive"))
      (node (ref "U$1") (pin "P$1") (pinfunction "KL_P$1") (pintype "passive"))
      (node (ref "U$1") (pin "P$2") (pinfunction "KL_P$2") (pintype "passive"))
    )
    (net (code "61") (name "Net-(T1-A2)") (class "Default")
      (node (ref "F1") (pin "1") (pinfunction "1_1") (pintype "passive"))
      (node (ref "R2") (pin "2") (pinfunction "2_2") (pintype "passive"))
      (node (ref "T1") (pin "T2") (pinfunction "A2_T2") (pintype "passive"))
    )
    (net (code "62") (name "Net-(X9A-KL)") (class "Default")
      (node (ref "R26") (pin "1") (pinfunction "1_1") (pintype "passive"))
      (node (ref "X9") (pin "1") (pinfunction "KL_1") (pintype "passive"))
    )
    (net (code "63") (name "Net-(X9B-KL)") (class "Default")
      (node (ref "R27") (pin "1") (pinfunction "1_1") (pintype "passive"))
      (node (ref "X9") (pin "2") (pinfunction "KL_2") (pintype "passive"))
    )
    (net (code "64") (name "Net-(X10B-1)") (class "Default")
      (node (ref "D1") (pin "A") (pinfunction "A_A") (pintype "passive"))
      (node (ref "X10") (pin "2") (pinfunction "1_2") (pintype "passive"))
    )
    (net (code "65") (name "Net-(X11B-1)") (class "Default")
      (node (ref "D2") (pin "A") (pinfunction "A_A") (pintype "passive"))
      (node (ref "X11") (pin "2") (pinfunction "1_2") (pintype "passive"))
    )
    (net (code "66") (name "Net-(X12B-1)") (class "Default")
      (node (ref "D3") (pin "A") (pinfunction "A_A") (pintype "passive"))
      (node (ref "X12") (pin "2") (pinfunction "1_2") (pintype "passive"))
    )
    (net (code "67") (name "Net-(X13B-1)") (class "Default")
      (node (ref "D4") (pin "A") (pinfunction "A_A") (pintype "passive"))
      (node (ref "X13") (pin "2") (pinfunction "1_2") (pintype "passive"))
    )
    (net (code "68") (name "Net-(X14B-1)") (class "Default")
      (node (ref "D5") (pin "A") (pinfunction "A_A") (pintype "passive"))
      (node (ref "X14") (pin "2") (pinfunction "1_2") (pintype "passive"))
    )
    (net (code "69") (name "Net-(X15B-1)") (class "Default")
      (node (ref "D6") (pin "A") (pinfunction "A_A") (pintype "passive"))
      (node (ref "X15") (pin "2") (pinfunction "1_2") (pintype "passive"))
    )
    (net (code "70") (name "Net-(X16B-1)") (class "Default")
      (node (ref "D7") (pin "A") (pinfunction "A_A") (pintype "passive"))
      (node (ref "X16") (pin "2") (pinfunction "1_2") (pintype "passive"))
    )
    (net (code "71") (name "Net-(X17B-1)") (class "Default")
      (node (ref "D8") (pin "A") (pinfunction "A_A") (pintype "passive"))
      (node (ref "X17") (pin "2") (pinfunction "1_2") (pintype "passive"))
    )
    (net (code "72") (name "Net-(X18B-1)") (class "Default")
      (node (ref "D9") (pin "A") (pinfunction "A_A") (pintype "passive"))
      (node (ref "X18") (pin "2") (pinfunction "1_2") (pintype "passive"))
    )
    (net (code "73") (name "Net-(X19B-1)") (class "Default")
      (node (ref "D10") (pin "A") (pinfunction "A_A") (pintype "passive"))
      (node (ref "X19") (pin "2") (pinfunction "1_2") (pintype "passive"))
    )
    (net (code "74") (name "Net-(X20B-1)") (class "Default")
      (node (ref "D11") (pin "A") (pinfunction "A_A") (pintype "passive"))
      (node (ref "X20") (pin "2") (pinfunction "1_2") (pintype "passive"))
    )
    (net (code "75") (name "Net-(X21B-1)") (class "Default")
      (node (ref "D12") (pin "A") (pinfunction "A_A") (pintype "passive"))
      (node (ref "X21") (pin "2") (pinfunction "1_2") (pintype "passive"))
    )
    (net (code "76") (name "Net-(X22B-1)") (class "Default")
      (node (ref "D13") (pin "A") (pinfunction "A_A") (pintype "passive"))
      (node (ref "X22") (pin "2") (pinfunction "1_2") (pintype "passive"))
    )
    (net (code "77") (name "Net-(X23B-1)") (class "Default")
      (node (ref "D14") (pin "A") (pinfunction "A_A") (pintype "passive"))
      (node (ref "X23") (pin "2") (pinfunction "1_2") (pintype "passive"))
    )
    (net (code "78") (name "Net-(X24B-1)") (class "Default")
      (node (ref "D15") (pin "A") (pinfunction "A_A") (pintype "passive"))
      (node (ref "X24") (pin "2") (pinfunction "1_2") (pintype "passive"))
    )
    (net (code "79") (name "Net-(X25B-1)") (class "Default")
      (node (ref "D16") (pin "A") (pinfunction "A_A") (pintype "passive"))
      (node (ref "X25") (pin "2") (pinfunction "1_2") (pintype "passive"))
    )
    (net (code "80") (name "Net-(X26B-1)") (class "Default")
      (node (ref "D17") (pin "A") (pinfunction "A_A") (pintype "passive"))
      (node (ref "X26") (pin "2") (pinfunction "1_2") (pintype "passive"))
    )
    (net (code "81") (name "Net-(X27B-1)") (class "Default")
      (node (ref "D18") (pin "A") (pinfunction "A_A") (pintype "passive"))
      (node (ref "X27") (pin "2") (pinfunction "1_2") (pintype "passive"))
    )
    (net (code "82") (name "Net-(X28B-1)") (class "Default")
      (node (ref "D19") (pin "A") (pinfunction "A_A") (pintype "passive"))
      (node (ref "X28") (pin "2") (pinfunction "1_2") (pintype "passive"))
    )
    (net (code "83") (name "Net-(X29B-1)") (class "Default")
      (node (ref "D20") (pin "A") (pinfunction "A_A") (pintype "passive"))
      (node (ref "X29") (pin "2") (pinfunction "1_2") (pintype "passive"))
    )
    (net (code "84") (name "Net-(X30B-1)") (class "Default")
      (node (ref "D21") (pin "A") (pinfunction "A_A") (pintype "passive"))
      (node (ref "X30") (pin "2") (pinfunction "1_2") (pintype "passive"))
    )
    (net (code "85") (name "Net-(X31B-1)") (class "Default")
      (node (ref "D22") (pin "A") (pinfunction "A_A") (pintype "passive"))
      (node (ref "X31") (pin "2") (pinfunction "1_2") (pintype "passive"))
    )
    (net (code "86") (name "Net-(X32B-1)") (class "Default")
      (node (ref "D23") (pin "A") (pinfunction "A_A") (pintype "passive"))
      (node (ref "X32") (pin "2") (pinfunction "1_2") (pintype "passive"))
    )
    (net (code "87") (name "Net-(X33B-1)") (class "Default")
      (node (ref "D24") (pin "A") (pinfunction "A_A") (pintype "passive"))
      (node (ref "X33") (pin "2") (pinfunction "1_2") (pintype "passive"))
    )
    (net (code "88") (name "Net-(X34B-1)") (class "Default")
      (node (ref "D25") (pin "A") (pinfunction "A_A") (pintype "passive"))
      (node (ref "X34") (pin "2") (pinfunction "1_2") (pintype "passive"))
    )
    (net (code "89") (name "VCC") (class "Default")
      (node (ref "C4") (pin "1") (pinfunction "1_1") (pintype "passive"))
      (node (ref "C5") (pin "1") (pinfunction "1_1") (pintype "passive"))
      (node (ref "IC1") (pin "17") (pinfunction "VCC1_17") (pintype "power_in"))
      (node (ref "IC1") (pin "38") (pinfunction "VCC2_38") (pintype "power_in"))
      (node (ref "IC1") (pin "5") (pinfunction "VCC_5") (pintype "power_in"))
      (node (ref "L1") (pin "1") (pinfunction "1_1") (pintype "passive"))
      (node (ref "R28") (pin "2") (pinfunction "2_2") (pintype "passive"))
      (node (ref "X1") (pin "3") (pinfunction "1_3") (pintype "passive"))
      (node (ref "X2") (pin "3") (pinfunction "1_3") (pintype "passive"))
      (node (ref "X3") (pin "3") (pinfunction "1_3") (pintype "passive"))
      (node (ref "X4") (pin "3") (pinfunction "1_3") (pintype "passive"))
      (node (ref "X5") (pin "3") (pinfunction "1_3") (pintype "passive"))
      (node (ref "X6") (pin "3") (pinfunction "1_3") (pintype "passive"))
      (node (ref "X7") (pin "3") (pinfunction "1_3") (pintype "passive"))
      (node (ref "X8") (pin "3") (pinfunction "1_3") (pintype "passive"))
    )
    (net (code "90") (name "unconnected-(IC1-(AIN1{slash}OC0)PB3-Pad43)") (class "Default")
      (node (ref "IC1") (pin "43") (pinfunction "(AIN1/OC0)PB3_43") (pintype "bidirectional"))
    )
    (net (code "91") (name "unconnected-(IC1-(SS)PB4-Pad44)") (class "Default")
      (node (ref "IC1") (pin "44") (pinfunction "(SS)PB4_44") (pintype "bidirectional"))
    )
    (net (code "92") (name "unconnected-(IC1-(T0{slash}XCK)PB0-Pad40)") (class "Default")
      (node (ref "IC1") (pin "40") (pinfunction "(T0/XCK)PB0_40") (pintype "bidirectional"))
    )
    (net (code "93") (name "unconnected-(IC1-(T1)PB1-Pad41)") (class "Default")
      (node (ref "IC1") (pin "41") (pinfunction "(T1)PB1_41") (pintype "bidirectional"))
    )
    (net (code "94") (name "unconnected-(IC1-(TMS)PC3-Pad22)") (class "Default")
      (node (ref "IC1") (pin "22") (pinfunction "(TMS)PC3_22") (pintype "bidirectional"))
    )
    (net (code "95") (name "unconnected-(IC1-AREF-Pad29)") (class "Default")
      (node (ref "IC1") (pin "29") (pinfunction "AREF_29") (pintype "passive"))
    )
    (net (code "96") (name "unconnected-(SV2-Pad6)") (class "Default")
      (node (ref "SV2") (pin "6") (pinfunction "6_6") (pintype "passive"))
    )
  )
)
